# untitled.net
KiCad netlist of a schematic drawn in EAGLE
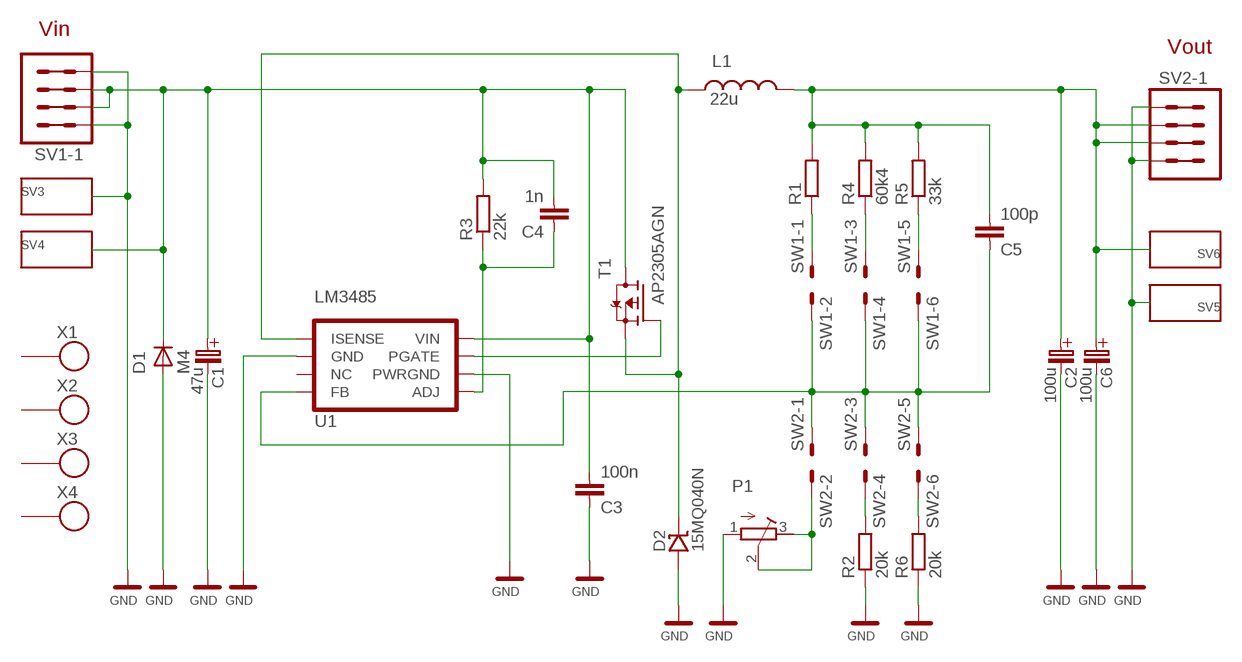
[diagram p0: schematic, sheet 1]

(export (version "E")
  (design (tool "Eeschema 10.0.6"))
  (components
    (comp (ref "C1") (value "47u") (footprint "eagle-import:C") (libsource (lib "eagle-import") (part "C")))
    (comp (ref "C2") (value "100u") (footprint "eagle-import:C") (libsource (lib "eagle-import") (part "C")))
    (comp (ref "C3")
      (value "100n")
      (footprint "eagle-import:C0805")
      (libsource (lib "eagle-import") (part "C0805"))
    )
    (comp (ref "C4")
      (value "1n")
      (footprint "eagle-import:C0805")
      (libsource (lib "eagle-import") (part "C0805"))
    )
    (comp (ref "C5")
      (value "100p")
      (footprint "eagle-import:C0805")
      (libsource (lib "eagle-import") (part "C0805"))
    )
    (comp (ref "C6") (value "100u") (footprint "eagle-import:C") (libsource (lib "eagle-import") (part "C")))
    (comp (ref "D1")
      (value "M4")
      (footprint "eagle-import:SMA")
      (libsource (lib "eagle-import") (part "D-OB.SMA"))
    )
    (comp (ref "D2")
      (value "15MQ040N")
      (footprint "eagle-import:SMA")
      (libsource (lib "eagle-import") (part "D-SHOTKY-SMA"))
    )
    (comp (ref "L1")
      (value "22u")
      (footprint "eagle-import:DE1205-10")
      (libsource (lib "eagle-import") (part "DE1205-10"))
    )
    (comp (ref "P1")
      (value "TRIMR_CA6XV")
      (footprint "eagle-import:TRIM_CA6XV")
      (libsource (lib "eagle-import") (part "TRIMR_CA6XV"))
    )
    (comp (ref "R1")
      (value "R0805")
      (footprint "eagle-import:0805")
      (libsource (lib "eagle-import") (part "R0805"))
    )
    (comp (ref "R2")
      (value "20k")
      (footprint "eagle-import:0805")
      (libsource (lib "eagle-import") (part "R0805"))
    )
    (comp (ref "R3")
      (value "22k")
      (footprint "eagle-import:0805")
      (libsource (lib "eagle-import") (part "R0805"))
    )
    (comp (ref "R4")
      (value "60k4")
      (footprint "eagle-import:0805")
      (libsource (lib "eagle-import") (part "R0805"))
    )
    (comp (ref "R5")
      (value "33k")
      (footprint "eagle-import:0805")
      (libsource (lib "eagle-import") (part "R0805"))
    )
    (comp (ref "R6")
      (value "20k")
      (footprint "eagle-import:0805")
      (libsource (lib "eagle-import") (part "R0805"))
    )
    (comp (ref "SV1")
      (value "MA04-2")
      (footprint "eagle-import:MA04-2")
      (libsource (lib "eagle-import") (part "MA04-2"))
    )
    (comp (ref "SV2")
      (value "MA04-2")
      (footprint "eagle-import:MA04-2")
      (libsource (lib "eagle-import") (part "MA04-2"))
    )
    (comp (ref "SV3")
      (value "WAGO256")
      (footprint "eagle-import:WAGO256")
      (libsource (lib "eagle-import") (part "WAGO256"))
    )
    (comp (ref "SV4")
      (value "WAGO256")
      (footprint "eagle-import:WAGO256")
      (libsource (lib "eagle-import") (part "WAGO256"))
    )
    (comp (ref "SV5")
      (value "WAGO256")
      (footprint "eagle-import:WAGO256")
      (libsource (lib "eagle-import") (part "WAGO256"))
    )
    (comp (ref "SV6")
      (value "WAGO256")
      (footprint "eagle-import:WAGO256")
      (libsource (lib "eagle-import") (part "WAGO256"))
    )
    (comp (ref "SW1")
      (value "MA03-3")
      (footprint "eagle-import:MA03-2")
      (libsource (lib "eagle-import") (part "MA03-3"))
    )
    (comp (ref "SW2")
      (value "MA03-3")
      (footprint "eagle-import:MA03-2")
      (libsource (lib "eagle-import") (part "MA03-3"))
    )
    (comp (ref "T1")
      (value "AP2305AGN")
      (footprint "eagle-import:SOT23")
      (libsource (lib "eagle-import") (part "AP2305AGN"))
    )
    (comp (ref "U1")
      (value "LM3485")
      (footprint "eagle-import:MSOP-8")
      (libsource (lib "eagle-import") (part "LM3485"))
    )
    (comp (ref "X1")
      (value "SROUB3M")
      (footprint "eagle-import:SROUB3M")
      (libsource (lib "eagle-import") (part "SROUB3M"))
    )
    (comp (ref "X2")
      (value "SROUB3M")
      (footprint "eagle-import:SROUB3M")
      (libsource (lib "eagle-import") (part "SROUB3M"))
    )
    (comp (ref "X3")
      (value "SROUB3M")
      (footprint "eagle-import:SROUB3M")
      (libsource (lib "eagle-import") (part "SROUB3M"))
    )
    (comp (ref "X4")
      (value "SROUB3M")
      (footprint "eagle-import:SROUB3M")
      (libsource (lib "eagle-import") (part "SROUB3M"))
    )
  )
  (nets
    (net (code "1") (name "GND") (class "Default")
      (node (ref "C1") (pin "-") (pinfunction "C_EL-_-") (pintype "passive"))
      (node (ref "C2") (pin "-") (pinfunction "C_EL-_-") (pintype "passive"))
      (node (ref "C3") (pin "1") (pinfunction "1_1") (pintype "passive"))
      (node (ref "C6") (pin "-") (pinfunction "C_EL-_-") (pintype "passive"))
      (node (ref "D1") (pin "A") (pinfunction "A_A") (pintype "passive"))
      (node (ref "D2") (pin "A") (pinfunction "A_A") (pintype "passive"))
      (node (ref "P1") (pin "1") (pinfunction "1_1") (pintype "passive"))
      (node (ref "R2") (pin "1") (pinfunction "1_1") (pintype "passive"))
      (node (ref "R6") (pin "1") (pinfunction "1_1") (pintype "passive"))
      (node (ref "SV1") (pin "1") (pinfunction "K_1") (pintype "passive"))
      (node (ref "SV1") (pin "2") (pinfunction "K_2") (pintype "passive"))
      (node (ref "SV1") (pin "7") (pinfunction "K_7") (pintype "passive"))
      (node (ref "SV1") (pin "8") (pinfunction "K_8") (pintype "passive"))
      (node (ref "SV2") (pin "1") (pinfunction "K_1") (pintype "passive"))
      (node (ref "SV2") (pin "2") (pinfunction "K_2") (pintype "passive"))
      (node (ref "SV2") (pin "7") (pinfunction "K_7") (pintype "passive"))
      (node (ref "SV2") (pin "8") (pinfunction "K_8") (pintype "passive"))
      (node (ref "SV3") (pin "1") (pinfunction "P$1_1") (pintype "passive"))
      (node (ref "SV3") (pin "A1") (pinfunction "P$1_A1") (pintype "passive"))
      (node (ref "SV5") (pin "1") (pinfunction "P$1_1") (pintype "passive"))
      (node (ref "SV5") (pin "A1") (pinfunction "P$1_A1") (pintype "passive"))
      (node (ref "U1") (pin "2") (pinfunction "GND_2") (pintype "passive"))
      (node (ref "U1") (pin "6") (pinfunction "PWRGND_6") (pintype "passive"))
    )
    (net (code "2") (name "Net-(C1-C_EL+)") (class "Default")
      (node (ref "C1") (pin "+") (pinfunction "C_EL+_+") (pintype "passive"))
      (node (ref "C3") (pin "2") (pinfunction "2_2") (pintype "passive"))
      (node (ref "C4") (pin "2") (pinfunction "2_2") (pintype "passive"))
      (node (ref "D1") (pin "K") (pinfunction "C_K") (pintype "passive"))
      (node (ref "R3") (pin "2") (pinfunction "2_2") (pintype "passive"))
      (node (ref "SV1") (pin "3") (pinfunction "K_3") (pintype "passive"))
      (node (ref "SV1") (pin "4") (pinfunction "K_4") (pintype "passive"))
      (node (ref "SV1") (pin "5") (pinfunction "K_5") (pintype "passive"))
      (node (ref "SV1") (pin "6") (pinfunction "K_6") (pintype "passive"))
      (node (ref "SV4") (pin "1") (pinfunction "P$1_1") (pintype "passive"))
      (node (ref "SV4") (pin "A1") (pinfunction "P$1_A1") (pintype "passive"))
      (node (ref "T1") (pin "3") (pinfunction "D_3") (pintype "passive"))
      (node (ref "U1") (pin "8") (pinfunction "VIN_8") (pintype "passive"))
    )
    (net (code "3") (name "Net-(C2-C_EL+)") (class "Default")
      (node (ref "C2") (pin "+") (pinfunction "C_EL+_+") (pintype "passive"))
      (node (ref "C5") (pin "2") (pinfunction "2_2") (pintype "passive"))
      (node (ref "C6") (pin "+") (pinfunction "C_EL+_+") (pintype "passive"))
      (node (ref "L1") (pin "P$2") (pinfunction "2_P$2") (pintype "passive"))
      (node (ref "R1") (pin "2") (pinfunction "2_2") (pintype "passive"))
      (node (ref "R4") (pin "2") (pinfunction "2_2") (pintype "passive"))
      (node (ref "R5") (pin "2") (pinfunction "2_2") (pintype "passive"))
      (node (ref "SV2") (pin "3") (pinfunction "K_3") (pintype "passive"))
      (node (ref "SV2") (pin "4") (pinfunction "K_4") (pintype "passive"))
      (node (ref "SV2") (pin "5") (pinfunction "K_5") (pintype "passive"))
      (node (ref "SV2") (pin "6") (pinfunction "K_6") (pintype "passive"))
      (node (ref "SV6") (pin "1") (pinfunction "P$1_1") (pintype "passive"))
      (node (ref "SV6") (pin "A1") (pinfunction "P$1_A1") (pintype "passive"))
    )
    (net (code "4") (name "Net-(L1-1)") (class "Default")
      (node (ref "D2") (pin "K") (pinfunction "K_K") (pintype "passive"))
      (node (ref "L1") (pin "P$1") (pinfunction "1_P$1") (pintype "passive"))
      (node (ref "T1") (pin "2") (pinfunction "S_2") (pintype "passive"))
      (node (ref "U1") (pin "1") (pinfunction "ISENSE_1") (pintype "passive"))
    )
    (net (code "5") (name "Net-(SW1A-P$1)") (class "Default")
      (node (ref "R1") (pin "1") (pinfunction "1_1") (pintype "passive"))
      (node (ref "SW1") (pin "1") (pinfunction "P$1_1") (pintype "passive"))
    )
    (net (code "6") (name "Net-(SW1B-P$1)") (class "Default")
      (node (ref "C5") (pin "1") (pinfunction "1_1") (pintype "passive"))
      (node (ref "SW1") (pin "2") (pinfunction "P$1_2") (pintype "passive"))
      (node (ref "SW1") (pin "4") (pinfunction "P$1_4") (pintype "passive"))
      (node (ref "SW1") (pin "6") (pinfunction "P$1_6") (pintype "passive"))
      (node (ref "SW2") (pin "1") (pinfunction "P$1_1") (pintype "passive"))
      (node (ref "SW2") (pin "3") (pinfunction "P$1_3") (pintype "passive"))
      (node (ref "SW2") (pin "5") (pinfunction "P$1_5") (pintype "passive"))
      (node (ref "U1") (pin "4") (pinfunction "FB_4") (pintype "passive"))
    )
    (net (code "7") (name "Net-(SW1C-P$1)") (class "Default")
      (node (ref "R4") (pin "1") (pinfunction "1_1") (pintype "passive"))
      (node (ref "SW1") (pin "3") (pinfunction "P$1_3") (pintype "passive"))
    )
    (net (code "8") (name "Net-(SW1E-P$1)") (class "Default")
      (node (ref "R5") (pin "1") (pinfunction "1_1") (pintype "passive"))
      (node (ref "SW1") (pin "5") (pinfunction "P$1_5") (pintype "passive"))
    )
    (net (code "9") (name "Net-(SW2B-P$1)") (class "Default")
      (node (ref "P1") (pin "2") (pinfunction "2_2") (pintype "passive"))
      (node (ref "P1") (pin "3") (pinfunction "3_3") (pintype "passive"))
      (node (ref "SW2") (pin "2") (pinfunction "P$1_2") (pintype "passive"))
    )
    (net (code "10") (name "Net-(SW2D-P$1)") (class "Default")
      (node (ref "R2") (pin "2") (pinfunction "2_2") (pintype "passive"))
      (node (ref "SW2") (pin "4") (pinfunction "P$1_4") (pintype "passive"))
    )
    (net (code "11") (name "Net-(SW2F-P$1)") (class "Default")
      (node (ref "R6") (pin "2") (pinfunction "2_2") (pintype "passive"))
      (node (ref "SW2") (pin "6") (pinfunction "P$1_6") (pintype "passive"))
    )
    (net (code "12") (name "Net-(T1-G)") (class "Default")
      (node (ref "T1") (pin "1") (pinfunction "G_1") (pintype "passive"))
      (node (ref "U1") (pin "7") (pinfunction "PGATE_7") (pintype "passive"))
    )
    (net (code "13") (name "Net-(U1-ADJ)") (class "Default")
      (node (ref "C4") (pin "1") (pinfunction "1_1") (pintype "passive"))
      (node (ref "R3") (pin "1") (pinfunction "1_1") (pintype "passive"))
      (node (ref "U1") (pin "5") (pinfunction "ADJ_5") (pintype "passive"))
    )
    (net (code "14") (name "unconnected-(U1-NC-Pad3)") (class "Default")
      (node (ref "U1") (pin "3") (pinfunction "NC_3") (pintype "passive"))
    )
    (net (code "15") (name "unconnected-(X1-PadP$1)") (class "Default")
      (node (ref "X1") (pin "P$1") (pinfunction "P$1_P$1") (pintype "bidirectional"))
    )
    (net (code "16") (name "unconnected-(X2-PadP$1)") (class "Default")
      (node (ref "X2") (pin "P$1") (pinfunction "P$1_P$1") (pintype "bidirectional"))
    )
    (net (code "17") (name "unconnected-(X3-PadP$1)") (class "Default")
      (node (ref "X3") (pin "P$1") (pinfunction "P$1_P$1") (pintype "bidirectional"))
    )
    (net (code "18") (name "unconnected-(X4-PadP$1)") (class "Default")
      (node (ref "X4") (pin "P$1") (pinfunction "P$1_P$1") (pintype "bidirectional"))
    )
  )
)
